# USB.net
KiCad netlist of a schematic drawn in Altium Designer
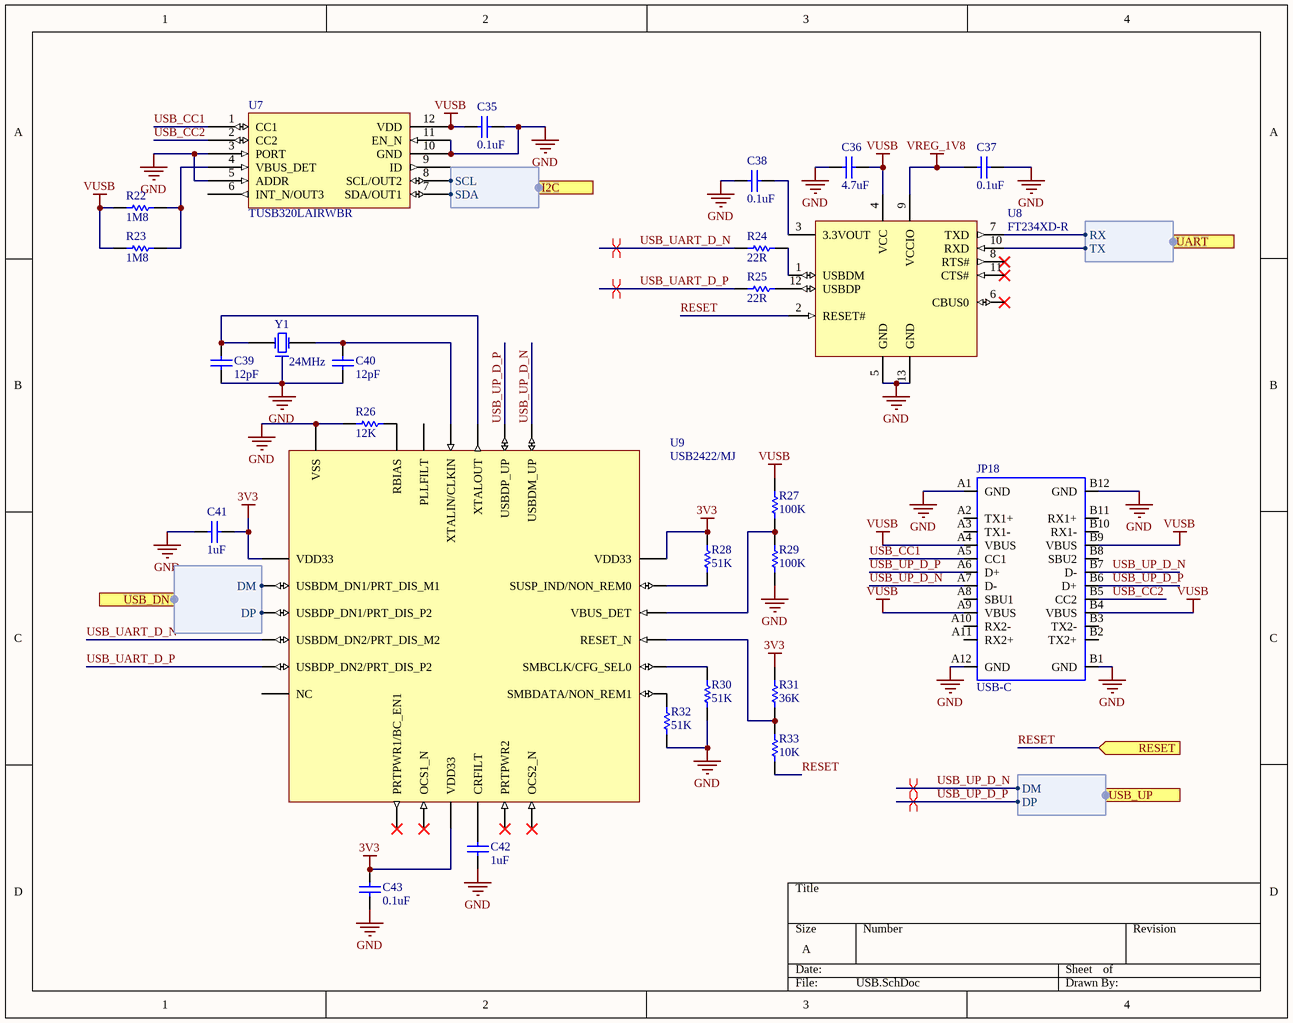
[diagram p0: USB.SchDoc]

(export (version "E")
  (design (tool "Eeschema 10.0.6"))
  (components
    (comp (ref "C35")
      (value "0.1uF")
      (footprint "C0402[1005X55]")
      (description "0.1uF 6.3V 10% 0402 (1005 Metric)")
      (fields (field (name "PARTNUMBER") "GRM155R70J104KA01D") (field (name "MANUFACTURER") "Murata"))
      (libsource (lib "Capacitors") (part "CAP_0.1uF_6.3V_0402_10%"))
    )
    (comp (ref "C36")
      (value "4.7uF")
      (footprint "C0402[1005X55]")
      (description "4.7uF 6.3V 20% 0402 (1005 Metric)")
      (fields (field (name "PARTNUMBER") "GRM155R60J475ME47D") (field (name "MANUFACTURER") "Murata"))
      (libsource (lib "Capacitors") (part "CAP_4.7uF_6.3V_0402_20%"))
    )
    (comp (ref "C37")
      (value "0.1uF")
      (footprint "C0402[1005X55]")
      (description "0.1uF 6.3V 10% 0402 (1005 Metric)")
      (fields (field (name "PARTNUMBER") "GRM155R70J104KA01D") (field (name "MANUFACTURER") "Murata"))
      (libsource (lib "Capacitors") (part "CAP_0.1uF_6.3V_0402_10%"))
    )
    (comp (ref "C38")
      (value "0.1uF")
      (footprint "C0402[1005X55]")
      (description "0.1uF 6.3V 10% 0402 (1005 Metric)")
      (fields (field (name "PARTNUMBER") "GRM155R70J104KA01D") (field (name "MANUFACTURER") "Murata"))
      (libsource (lib "Capacitors") (part "CAP_0.1uF_6.3V_0402_10%"))
    )
    (comp (ref "C39")
      (value "12pF")
      (footprint "C0402[1005X55]")
      (description "12pF 50V 5% 0402 (1005 Metric)")
      (fields (field (name "PARTNUMBER") "GRM1555C1H120JA01D") (field (name "MANUFACTURER") "Murata"))
      (libsource (lib "Capacitors") (part "CAP_12pF_50V_0402_5%"))
    )
    (comp (ref "C40")
      (value "12pF")
      (footprint "C0402[1005X55]")
      (description "12pF 50V 5% 0402 (1005 Metric)")
      (fields (field (name "PARTNUMBER") "GRM1555C1H120JA01D") (field (name "MANUFACTURER") "Murata"))
      (libsource (lib "Capacitors") (part "CAP_12pF_50V_0402_5%"))
    )
    (comp (ref "C41")
      (value "1uF")
      (footprint "C0402[1005X55]")
      (description "1uF 6.3V 10% 0402 (1005 Metric)")
      (fields (field (name "PARTNUMBER") "GRM155R70J105KA12D") (field (name "MANUFACTURER") "Murata"))
      (libsource (lib "Capacitors") (part "CAP_1uF_6.3V_0402_10%"))
    )
    (comp (ref "C42")
      (value "1uF")
      (footprint "C0402[1005X55]")
      (description "1uF 6.3V 10% 0402 (1005 Metric)")
      (fields (field (name "PARTNUMBER") "GRM155R70J105KA12D") (field (name "MANUFACTURER") "Murata"))
      (libsource (lib "Capacitors") (part "CAP_1uF_6.3V_0402_10%"))
    )
    (comp (ref "C43")
      (value "0.1uF")
      (footprint "C0402[1005X55]")
      (description "0.1uF 6.3V 10% 0402 (1005 Metric)")
      (fields (field (name "PARTNUMBER") "GRM155R70J104KA01D") (field (name "MANUFACTURER") "Murata"))
      (libsource (lib "Capacitors") (part "CAP_0.1uF_6.3V_0402_10%"))
    )
    (comp (ref "JP18")
      (value "USB-C")
      (footprint "USB-C-3.1")
      (fields (field (name "PARTNUMBER") "12401610E4#2A") (field (name "MANUFACTURER") "Amphenol FCI"))
      (libsource (lib "Connectors") (part "USB_C_3.1_SMT"))
    )
    (comp (ref "R22")
      (value "1M8")
      (footprint "R0402[1005]")
      (description "1M8 0.063W 1% 0402 (1005 Metric)")
      (fields (field (name "MANUFACTURER") "KOA Speer") (field (name "PARTNUMBER") "RK73H1ETTP1804F"))
      (libsource (lib "Resistors") (part "RES_1M8_0402_1%"))
    )
    (comp (ref "R23")
      (value "1M8")
      (footprint "R0402[1005]")
      (description "1M8 0.063W 1% 0402 (1005 Metric)")
      (fields (field (name "MANUFACTURER") "KOA Speer") (field (name "PARTNUMBER") "RK73H1ETTP1804F"))
      (libsource (lib "Resistors") (part "RES_1M8_0402_1%"))
    )
    (comp (ref "R24")
      (value "22R")
      (footprint "R0402[1005]")
      (description "22R 0.063W 1% 0402 (1005 Metric)")
      (fields (field (name "MANUFACTURER") "KOA Speer") (field (name "PARTNUMBER") "RK73H1ETTP22R0F"))
      (libsource (lib "Resistors") (part "RES_22R_0402_1%"))
    )
    (comp (ref "R25")
      (value "22R")
      (footprint "R0402[1005]")
      (description "22R 0.063W 1% 0402 (1005 Metric)")
      (fields (field (name "MANUFACTURER") "KOA Speer") (field (name "PARTNUMBER") "RK73H1ETTP22R0F"))
      (libsource (lib "Resistors") (part "RES_22R_0402_1%"))
    )
    (comp (ref "R26")
      (value "12K")
      (footprint "R0402[1005]")
      (description "12K 0.063W 1% 0402 (1005 Metric)")
      (fields (field (name "MANUFACTURER") "KOA Speer") (field (name "PARTNUMBER") "RK73H1ETTP1202F"))
      (libsource (lib "Resistors") (part "RES_12K_0402_1%"))
    )
    (comp (ref "R27")
      (value "100K")
      (footprint "R0402[1005]")
      (description "100K 0.063W 1% 0402 (1005 Metric)")
      (fields (field (name "MANUFACTURER") "KOA Speer") (field (name "PARTNUMBER") "RK73H1ETTP1003F"))
      (libsource (lib "Resistors") (part "RES_100K_0402_1%"))
    )
    (comp (ref "R28")
      (value "51K")
      (footprint "R0402[1005]")
      (description "51K 0.063W 1% 0402 (1005 Metric)")
      (fields (field (name "MANUFACTURER") "KOA Speer") (field (name "PARTNUMBER") "RK73H1ETTP5102F"))
      (libsource (lib "Resistors") (part "RES_51K_0402_1%"))
    )
    (comp (ref "R29")
      (value "100K")
      (footprint "R0402[1005]")
      (description "100K 0.063W 1% 0402 (1005 Metric)")
      (fields (field (name "MANUFACTURER") "KOA Speer") (field (name "PARTNUMBER") "RK73H1ETTP1003F"))
      (libsource (lib "Resistors") (part "RES_100K_0402_1%"))
    )
    (comp (ref "R30")
      (value "51K")
      (footprint "R0402[1005]")
      (description "51K 0.063W 1% 0402 (1005 Metric)")
      (fields (field (name "MANUFACTURER") "KOA Speer") (field (name "PARTNUMBER") "RK73H1ETTP5102F"))
      (libsource (lib "Resistors") (part "RES_51K_0402_1%"))
    )
    (comp (ref "R31")
      (value "36K")
      (footprint "R0402[1005]")
      (description "36K 0.063W 1% 0402 (1005 Metric)")
      (fields (field (name "MANUFACTURER") "KOA Speer") (field (name "PARTNUMBER") "RK73H1ETTP3602F"))
      (libsource (lib "Resistors") (part "RES_36K_0402_1%"))
    )
    (comp (ref "R32")
      (value "51K")
      (footprint "R0402[1005]")
      (description "51K 0.063W 1% 0402 (1005 Metric)")
      (fields (field (name "MANUFACTURER") "KOA Speer") (field (name "PARTNUMBER") "RK73H1ETTP5102F"))
      (libsource (lib "Resistors") (part "RES_51K_0402_1%"))
    )
    (comp (ref "R33")
      (value "10K")
      (footprint "R0402[1005]")
      (description "10K 0.063W 1% 0402 (1005 Metric)")
      (fields (field (name "MANUFACTURER") "KOA Speer") (field (name "PARTNUMBER") "RK73H1ETTP1002F"))
      (libsource (lib "Resistors") (part "RES_10K_0402_1%"))
    )
    (comp (ref "U7")
      (value "TUSB320LAIRWBR")
      (footprint "X2QFN-12")
      (description "USB Interface IC Type-C Configuration Channel Logic and Port Control 12-X2QFN -40 to 85")
      (fields (field (name "MANUFACTURER") "Texas Instruments"))
      (libsource (lib "ICs") (part "TUSB320LAIRWBR"))
    )
    (comp (ref "U8")
      (value "FT234XD-R")
      (footprint "DFN-12")
      (description "USB Interface IC USB to Serial UART Interface")
      (fields (field (name "MANUFACTURER") "FTDI"))
      (libsource (lib "ICs") (part "FT234XD-R"))
    )
    (comp (ref "U9")
      (value "USB2422/MJ")
      (footprint "QFN-24 (4x4MM)")
      (description "USB Hub IC 2-Port")
      (fields (field (name "MANUFACTURER") "Microchip"))
      (libsource (lib "ICs-USBInterface") (part "USB2422/MJ"))
    )
    (comp (ref "Y1")
      (value "24MHz")
      (footprint "CRYSTAL_2.0x1.6")
      (fields (field (name "PARTNUMBER") "FA-128 24.0000MF10Z-W3") (field (name "MANUFACTURER") "EPSON"))
      (libsource (lib "Components") (part "FA-128 24.0000MF10Z-W3"))
    )
  )
  (nets
    (net (code "4") (name "/RESET") (class "Default")
      (node (ref "R33") (pin "1") (pinfunction "1_1") (pintype "passive"))
      (node (ref "U8") (pin "2") (pinfunction "RESET#_2") (pintype "input"))
    )
    (net (code "5") (name "/RX") (class "Default")
      (node (ref "U8") (pin "7") (pinfunction "TXD_7") (pintype "output"))
    )
    (net (code "6") (name "/SCL") (class "Default")
      (node (ref "U7") (pin "8") (pinfunction "SCL/OUT2_8") (pintype "bidirectional"))
    )
    (net (code "7") (name "/SDA") (class "Default")
      (node (ref "U7") (pin "7") (pinfunction "SDA/OUT1_7") (pintype "bidirectional"))
    )
    (net (code "8") (name "/TX") (class "Default")
      (node (ref "U8") (pin "10") (pinfunction "RXD_10") (pintype "input"))
    )
    (net (code "9") (name "/USB_CC1") (class "Default")
      (node (ref "JP18") (pin "A5") (pinfunction "CC1_A5") (pintype "passive"))
      (node (ref "U7") (pin "1") (pinfunction "CC1_1") (pintype "bidirectional"))
    )
    (net (code "10") (name "/USB_CC2") (class "Default")
      (node (ref "JP18") (pin "B5") (pinfunction "CC2_B5") (pintype "passive"))
      (node (ref "U7") (pin "2") (pinfunction "CC2_2") (pintype "bidirectional"))
    )
    (net (code "11") (name "/USB_UART_D_N") (class "Default")
      (node (ref "R24") (pin "1") (pinfunction "1_1") (pintype "passive"))
      (node (ref "U9") (pin "4") (pinfunction "USBDM_DN2/PRT_DIS_M2_4") (pintype "bidirectional"))
    )
    (net (code "12") (name "/USB_UART_D_P") (class "Default")
      (node (ref "R25") (pin "1") (pinfunction "1_1") (pintype "passive"))
      (node (ref "U9") (pin "5") (pinfunction "USBDP_DN2/PRT_DIS_P2_5") (pintype "bidirectional"))
    )
    (net (code "13") (name "/USB_UP_D_N") (class "Default")
      (node (ref "JP18") (pin "A7") (pinfunction "D-_A7") (pintype "passive"))
      (node (ref "JP18") (pin "B7") (pinfunction "D-_B7") (pintype "passive"))
      (node (ref "U9") (pin "19") (pinfunction "USBDM_UP_19") (pintype "bidirectional"))
    )
    (net (code "14") (name "/USB_UP_D_P") (class "Default")
      (node (ref "JP18") (pin "A6") (pinfunction "D+_A6") (pintype "passive"))
      (node (ref "JP18") (pin "B6") (pinfunction "D+_B6") (pintype "passive"))
      (node (ref "U9") (pin "20") (pinfunction "USBDP_UP_20") (pintype "bidirectional"))
    )
    (net (code "18") (name "3V3") (class "Default")
      (node (ref "C41") (pin "2") (pinfunction "2_2") (pintype "passive"))
      (node (ref "C43") (pin "2") (pinfunction "2_2") (pintype "passive"))
      (node (ref "R28") (pin "2") (pinfunction "2_2") (pintype "passive"))
      (node (ref "R31") (pin "2") (pinfunction "2_2") (pintype "passive"))
      (node (ref "U9") (pin "1") (pinfunction "VDD33_1") (pintype "power_in"))
      (node (ref "U9") (pin "18") (pinfunction "VDD33_18") (pintype "power_in"))
      (node (ref "U9") (pin "9") (pinfunction "VDD33_9") (pintype "power_in"))
    )
    (net (code "19") (name "GND") (class "Default")
      (node (ref "C35") (pin "1") (pinfunction "1_1") (pintype "passive"))
      (node (ref "C36") (pin "2") (pinfunction "2_2") (pintype "passive"))
      (node (ref "C37") (pin "1") (pinfunction "1_1") (pintype "passive"))
      (node (ref "C38") (pin "2") (pinfunction "2_2") (pintype "passive"))
      (node (ref "C39") (pin "1") (pinfunction "1_1") (pintype "passive"))
      (node (ref "C40") (pin "1") (pinfunction "1_1") (pintype "passive"))
      (node (ref "C41") (pin "1") (pinfunction "1_1") (pintype "passive"))
      (node (ref "C42") (pin "1") (pinfunction "1_1") (pintype "passive"))
      (node (ref "C43") (pin "1") (pinfunction "1_1") (pintype "passive"))
      (node (ref "JP18") (pin "A1") (pinfunction "GND_A1") (pintype "power_in"))
      (node (ref "JP18") (pin "A12") (pinfunction "GND_A12") (pintype "power_in"))
      (node (ref "JP18") (pin "B1") (pinfunction "GND_B1") (pintype "power_in"))
      (node (ref "JP18") (pin "B12") (pinfunction "GND_B12") (pintype "power_in"))
      (node (ref "R26") (pin "1") (pinfunction "1_1") (pintype "passive"))
      (node (ref "R29") (pin "1") (pinfunction "1_1") (pintype "passive"))
      (node (ref "R30") (pin "1") (pinfunction "1_1") (pintype "passive"))
      (node (ref "R32") (pin "1") (pinfunction "1_1") (pintype "passive"))
      (node (ref "U7") (pin "10") (pinfunction "GND_10") (pintype "power_in"))
      (node (ref "U7") (pin "11") (pinfunction "EN_N_11") (pintype "input"))
      (node (ref "U7") (pin "3") (pinfunction "PORT_3") (pintype "input"))
      (node (ref "U7") (pin "5") (pinfunction "ADDR_5") (pintype "input"))
      (node (ref "U8") (pin "13") (pinfunction "GND_13") (pintype "power_in"))
      (node (ref "U8") (pin "5") (pinfunction "GND_5") (pintype "power_in"))
      (node (ref "U9") (pin "25") (pinfunction "VSS_25") (pintype "power_in"))
      (node (ref "Y1") (pin "2") (pinfunction "2_2") (pintype "passive"))
    )
    (net (code "20") (name "Net-(U7-VBUS_DET)") (class "Default")
      (node (ref "R22") (pin "2") (pinfunction "2_2") (pintype "passive"))
      (node (ref "R23") (pin "2") (pinfunction "2_2") (pintype "passive"))
      (node (ref "U7") (pin "4") (pinfunction "VBUS_DET_4") (pintype "input"))
    )
    (net (code "21") (name "Net-(U8-3.3VOUT)") (class "Default")
      (node (ref "C38") (pin "1") (pinfunction "1_1") (pintype "passive"))
      (node (ref "U8") (pin "3") (pinfunction "3.3VOUT_3") (pintype "power_in"))
    )
    (net (code "22") (name "Net-(U8-USBDM)") (class "Default")
      (node (ref "R24") (pin "2") (pinfunction "2_2") (pintype "passive"))
      (node (ref "U8") (pin "1") (pinfunction "USBDM_1") (pintype "bidirectional"))
    )
    (net (code "23") (name "Net-(U8-USBDP)") (class "Default")
      (node (ref "R25") (pin "2") (pinfunction "2_2") (pintype "passive"))
      (node (ref "U8") (pin "12") (pinfunction "USBDP_12") (pintype "bidirectional"))
    )
    (net (code "24") (name "Net-(U9-CRFILT)") (class "Default")
      (node (ref "C42") (pin "2") (pinfunction "2_2") (pintype "passive"))
      (node (ref "U9") (pin "10") (pinfunction "CRFILT_10") (pintype "passive"))
    )
    (net (code "25") (name "Net-(U9-RBIAS)") (class "Default")
      (node (ref "R26") (pin "2") (pinfunction "2_2") (pintype "passive"))
      (node (ref "U9") (pin "24") (pinfunction "RBIAS_24") (pintype "passive"))
    )
    (net (code "26") (name "Net-(U9-RESET_N)") (class "Default")
      (node (ref "R31") (pin "1") (pinfunction "1_1") (pintype "passive"))
      (node (ref "R33") (pin "2") (pinfunction "2_2") (pintype "passive"))
      (node (ref "U9") (pin "15") (pinfunction "RESET_N_15") (pintype "input"))
    )
    (net (code "27") (name "Net-(U9-SMBCLK{slash}CFG_SEL0)") (class "Default")
      (node (ref "R30") (pin "2") (pinfunction "2_2") (pintype "passive"))
      (node (ref "U9") (pin "14") (pinfunction "SMBCLK/CFG_SEL0_14") (pintype "bidirectional"))
    )
    (net (code "28") (name "Net-(U9-SMBDATA{slash}NON_REM1)") (class "Default")
      (node (ref "R32") (pin "2") (pinfunction "2_2") (pintype "passive"))
      (node (ref "U9") (pin "13") (pinfunction "SMBDATA/NON_REM1_13") (pintype "bidirectional"))
    )
    (net (code "29") (name "Net-(U9-SUSP_IND{slash}NON_REM0)") (class "Default")
      (node (ref "R28") (pin "1") (pinfunction "1_1") (pintype "passive"))
      (node (ref "U9") (pin "17") (pinfunction "SUSP_IND/NON_REM0_17") (pintype "bidirectional"))
    )
    (net (code "30") (name "Net-(U9-VBUS_DET)") (class "Default")
      (node (ref "R27") (pin "1") (pinfunction "1_1") (pintype "passive"))
      (node (ref "R29") (pin "2") (pinfunction "2_2") (pintype "passive"))
      (node (ref "U9") (pin "16") (pinfunction "VBUS_DET_16") (pintype "input"))
    )
    (net (code "31") (name "Net-(U9-XTALIN{slash}CLKIN)") (class "Default")
      (node (ref "C40") (pin "2") (pinfunction "2_2") (pintype "passive"))
      (node (ref "U9") (pin "22") (pinfunction "XTALIN/CLKIN_22") (pintype "input"))
      (node (ref "Y1") (pin "3") (pinfunction "X2_3") (pintype "passive"))
    )
    (net (code "32") (name "Net-(U9-XTALOUT)") (class "Default")
      (node (ref "C39") (pin "2") (pinfunction "2_2") (pintype "passive"))
      (node (ref "U9") (pin "21") (pinfunction "XTALOUT_21") (pintype "output"))
      (node (ref "Y1") (pin "1") (pinfunction "X1_1") (pintype "passive"))
    )
    (net (code "33") (name "VREG_1V8") (class "Default")
      (node (ref "C37") (pin "2") (pinfunction "2_2") (pintype "passive"))
      (node (ref "U8") (pin "9") (pinfunction "VCCIO_9") (pintype "power_in"))
    )
    (net (code "34") (name "VUSB") (class "Default")
      (node (ref "C35") (pin "2") (pinfunction "2_2") (pintype "passive"))
      (node (ref "C36") (pin "1") (pinfunction "1_1") (pintype "passive"))
      (node (ref "JP18") (pin "A4") (pinfunction "VBUS_A4") (pintype "power_in"))
      (node (ref "JP18") (pin "A9") (pinfunction "VBUS_A9") (pintype "power_in"))
      (node (ref "JP18") (pin "B4") (pinfunction "VBUS_B4") (pintype "power_in"))
      (node (ref "JP18") (pin "B9") (pinfunction "VBUS_B9") (pintype "power_in"))
      (node (ref "R22") (pin "1") (pinfunction "1_1") (pintype "passive"))
      (node (ref "R23") (pin "1") (pinfunction "1_1") (pintype "passive"))
      (node (ref "R27") (pin "2") (pinfunction "2_2") (pintype "passive"))
      (node (ref "U7") (pin "12") (pinfunction "VDD_12") (pintype "power_in"))
      (node (ref "U8") (pin "4") (pinfunction "VCC_4") (pintype "power_in"))
    )
    (net (code "35") (name "unconnected-(JP18-RX1+-PadB11)") (class "Default")
      (node (ref "JP18") (pin "B11") (pinfunction "RX1+_B11") (pintype "passive"))
    )
    (net (code "36") (name "unconnected-(JP18-RX1--PadB10)") (class "Default")
      (node (ref "JP18") (pin "B10") (pinfunction "RX1-_B10") (pintype "passive"))
    )
    (net (code "37") (name "unconnected-(JP18-RX2+-PadA11)") (class "Default")
      (node (ref "JP18") (pin "A11") (pinfunction "RX2+_A11") (pintype "passive"))
    )
    (net (code "38") (name "unconnected-(JP18-RX2--PadA10)") (class "Default")
      (node (ref "JP18") (pin "A10") (pinfunction "RX2-_A10") (pintype "passive"))
    )
    (net (code "39") (name "unconnected-(JP18-SBU1-PadA8)") (class "Default")
      (node (ref "JP18") (pin "A8") (pinfunction "SBU1_A8") (pintype "passive"))
    )
    (net (code "40") (name "unconnected-(JP18-SBU2-PadB8)") (class "Default")
      (node (ref "JP18") (pin "B8") (pinfunction "SBU2_B8") (pintype "passive"))
    )
    (net (code "41") (name "unconnected-(JP18-TX1+-PadA2)") (class "Default")
      (node (ref "JP18") (pin "A2") (pinfunction "TX1+_A2") (pintype "passive"))
    )
    (net (code "42") (name "unconnected-(JP18-TX1--PadA3)") (class "Default")
      (node (ref "JP18") (pin "A3") (pinfunction "TX1-_A3") (pintype "passive"))
    )
    (net (code "43") (name "unconnected-(JP18-TX2+-PadB2)") (class "Default")
      (node (ref "JP18") (pin "B2") (pinfunction "TX2+_B2") (pintype "passive"))
    )
    (net (code "44") (name "unconnected-(JP18-TX2--PadB3)") (class "Default")
      (node (ref "JP18") (pin "B3") (pinfunction "TX2-_B3") (pintype "passive"))
    )
    (net (code "45") (name "unconnected-(U7-ID-Pad9)") (class "Default")
      (node (ref "U7") (pin "9") (pinfunction "ID_9") (pintype "output"))
    )
    (net (code "46") (name "unconnected-(U7-INT_N{slash}OUT3-Pad6)") (class "Default")
      (node (ref "U7") (pin "6") (pinfunction "INT_N/OUT3_6") (pintype "output"))
    )
    (net (code "47") (name "unconnected-(U8-CBUS0-Pad6)") (class "Default")
      (node (ref "U8") (pin "6") (pinfunction "CBUS0_6") (pintype "bidirectional+no_connect"))
    )
    (net (code "48") (name "unconnected-(U8-CTS#-Pad11)") (class "Default")
      (node (ref "U8") (pin "11") (pinfunction "CTS#_11") (pintype "input+no_connect"))
    )
    (net (code "49") (name "unconnected-(U8-RTS#-Pad8)") (class "Default")
      (node (ref "U8") (pin "8") (pinfunction "RTS#_8") (pintype "output+no_connect"))
    )
    (net (code "50") (name "unconnected-(U9-NC-Pad6)") (class "Default")
      (node (ref "U9") (pin "6") (pinfunction "NC_6") (pintype "passive"))
    )
    (net (code "51") (name "unconnected-(U9-OCS1_N-Pad8)") (class "Default")
      (node (ref "U9") (pin "8") (pinfunction "OCS1_N_8") (pintype "input+no_connect"))
    )
    (net (code "52") (name "unconnected-(U9-OCS2_N-Pad12)") (class "Default")
      (node (ref "U9") (pin "12") (pinfunction "OCS2_N_12") (pintype "input+no_connect"))
    )
    (net (code "53") (name "unconnected-(U9-PLLFILT-Pad23)") (class "Default")
      (node (ref "U9") (pin "23") (pinfunction "PLLFILT_23") (pintype "passive"))
    )
    (net (code "54") (name "unconnected-(U9-PRTPWR1{slash}BC_EN1-Pad7)") (class "Default")
      (node (ref "U9") (pin "7") (pinfunction "PRTPWR1/BC_EN1_7") (pintype "output+no_connect"))
    )
    (net (code "55") (name "unconnected-(U9-PRTPWR2-Pad11)") (class "Default")
      (node (ref "U9") (pin "11") (pinfunction "PRTPWR2_11") (pintype "input+no_connect"))
    )
    (net (code "56") (name "unconnected-(U9-USBDM_DN1{slash}PRT_DIS_M1-Pad2)") (class "Default")
      (node (ref "U9") (pin "2") (pinfunction "USBDM_DN1/PRT_DIS_M1_2") (pintype "bidirectional"))
    )
    (net (code "57") (name "unconnected-(U9-USBDP_DN1{slash}PRT_DIS_P2-Pad3)") (class "Default")
      (node (ref "U9") (pin "3") (pinfunction "USBDP_DN1/PRT_DIS_P2_3") (pintype "bidirectional"))
    )
  )
)
